# Robot-Power_V3_0.net
KiCad netlist of a schematic drawn in Altium Designer
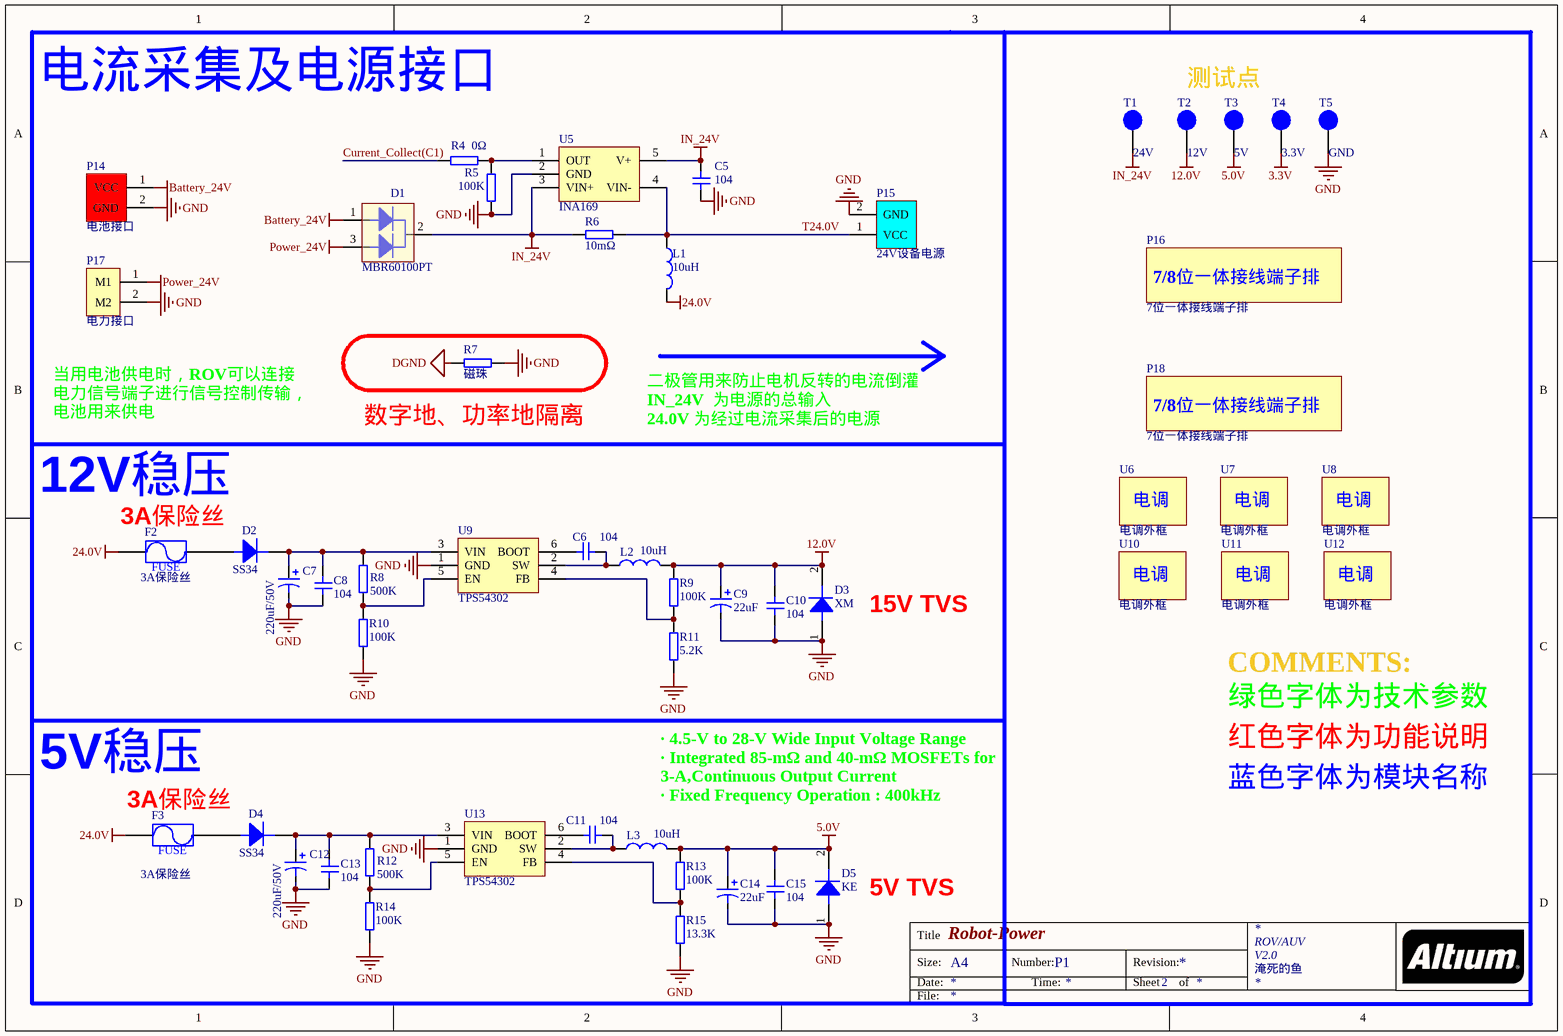
[diagram p0: Robot-Power V3.0.SchDoc]

(export (version "E")
  (design (tool "Eeschema 10.0.6"))
  (components
    (comp (ref "C5")
      (value "104")
      (footprint "0805C")
      (description "无极贴片电容")
      (libsource (lib "集大电协1.5") (part "Cap1"))
    )
    (comp (ref "C6")
      (value "104")
      (footprint "0805C")
      (description "无极贴片电容")
      (libsource (lib "集大电协1.5") (part "Cap1"))
    )
    (comp (ref "C7")
      (value "220uF/50V")
      (footprint "RB.1.2")
      (description "直插极性电容")
      (libsource (lib "集大电协1.5") (part "Cap3"))
    )
    (comp (ref "C8")
      (value "104")
      (footprint "0805C")
      (description "无极贴片电容")
      (libsource (lib "集大电协1.5") (part "Cap1"))
    )
    (comp (ref "C9")
      (value "22uF")
      (footprint "TAJ-C")
      (description "极性贴片电容")
      (libsource (lib "集大电协1.5") (part "Pol Cap"))
    )
    (comp (ref "C10")
      (value "104")
      (footprint "0805C")
      (description "无极贴片电容")
      (libsource (lib "集大电协1.5") (part "Cap1"))
    )
    (comp (ref "C11")
      (value "104")
      (footprint "0805C")
      (description "无极贴片电容")
      (libsource (lib "集大电协1.5") (part "Cap1"))
    )
    (comp (ref "C12")
      (value "220uF/50V")
      (footprint "RB.1.2")
      (description "直插极性电容")
      (libsource (lib "集大电协1.5") (part "Cap3"))
    )
    (comp (ref "C13")
      (value "104")
      (footprint "0805C")
      (description "无极贴片电容")
      (libsource (lib "集大电协1.5") (part "Cap1"))
    )
    (comp (ref "C14")
      (value "22uF")
      (footprint "TAJ-C")
      (description "极性贴片电容")
      (libsource (lib "集大电协1.5") (part "Pol Cap"))
    )
    (comp (ref "C15")
      (value "104")
      (footprint "0805C")
      (description "无极贴片电容")
      (libsource (lib "集大电协1.5") (part "Cap1"))
    )
    (comp (ref "D1")
      (value "MBR60100PT")
      (footprint "TO-247LS")
      (libsource (lib "集大电协1.5") (part "MBR60100PT"))
    )
    (comp (ref "D2")
      (value "SS34")
      (footprint "SMA/DO-214AC")
      (description "二极管")
      (libsource (lib "") (part "Diode_1"))
    )
    (comp (ref "D3")
      (value "XM")
      (footprint "SMBJ")
      (description "二极管")
      (libsource (lib "集大电协1.5") (part "Diode"))
    )
    (comp (ref "D4")
      (value "SS34")
      (footprint "SMA/DO-214AC")
      (description "二极管")
      (libsource (lib "") (part "Diode_1"))
    )
    (comp (ref "D5")
      (value "KE")
      (footprint "SMBJ")
      (description "二极管")
      (libsource (lib "集大电协1.5") (part "Diode"))
    )
    (comp (ref "F2")
      (value "3A保险丝")
      (footprint "FUSE-1206")
      (description "保险丝")
      (libsource (lib "集大电协1.2") (part "Fuse"))
    )
    (comp (ref "F3")
      (value "3A保险丝")
      (footprint "FUSE-1206")
      (description "保险丝")
      (libsource (lib "集大电协1.2") (part "Fuse"))
    )
    (comp (ref "L1")
      (value "10uH")
      (footprint "CDRH124")
      (description "电感")
      (libsource (lib "") (part "L_1"))
    )
    (comp (ref "L2")
      (value "10uH")
      (footprint "CDRH124")
      (description "电感")
      (libsource (lib "集大电协1.5") (part "L"))
    )
    (comp (ref "L3")
      (value "10uH")
      (footprint "CDRH124")
      (description "电感")
      (libsource (lib "集大电协1.5") (part "L"))
    )
    (comp (ref "P14") (value "电池接口") (footprint "XT60-F") (libsource (lib "集大电协1.5") (part "电源端子")))
    (comp (ref "P15") (value "24V设备电源") (footprint "XT60-F") (libsource (lib "集大电协1.5") (part "推进器电源")))
    (comp (ref "P16")
      (value "7位一体接线端子排")
      (footprint "7/8一体接线端子")
      (libsource (lib "集大电协1.5") (part "7位一体接线端子排"))
    )
    (comp (ref "P17")
      (value "电力接口")
      (footprint "XT60-F")
      (description "2PIN")
      (libsource (lib "集大电协1.5") (part "接线端子-2PIN"))
    )
    (comp (ref "P18")
      (value "7位一体接线端子排")
      (footprint "7/8一体接线端子")
      (libsource (lib "集大电协1.5") (part "7位一体接线端子排"))
    )
    (comp (ref "R4")
      (value "0Ω")
      (footprint "0805R")
      (description "电阻")
      (libsource (lib "集大电协1.5") (part "Res"))
    )
    (comp (ref "R5")
      (value "100K")
      (footprint "0805R")
      (description "电阻")
      (libsource (lib "集大电协1.5") (part "Res"))
    )
    (comp (ref "R6")
      (value "10mΩ")
      (footprint "2512R")
      (description "电阻")
      (libsource (lib "集大电协1.5") (part "Res"))
    )
    (comp (ref "R7")
      (value "磁珠")
      (footprint "1210R")
      (description "电阻")
      (libsource (lib "集大电协1.2") (part "Res"))
    )
    (comp (ref "R8")
      (value "500K")
      (footprint "0805R")
      (description "电阻")
      (libsource (lib "集大电协1.5") (part "Res"))
    )
    (comp (ref "R9")
      (value "100K")
      (footprint "0805R")
      (description "电阻")
      (libsource (lib "集大电协1.5") (part "Res"))
    )
    (comp (ref "R10")
      (value "100K")
      (footprint "0805R")
      (description "电阻")
      (libsource (lib "集大电协1.5") (part "Res"))
    )
    (comp (ref "R11")
      (value "5.2K")
      (footprint "0805R")
      (description "电阻")
      (libsource (lib "集大电协1.5") (part "Res"))
    )
    (comp (ref "R12")
      (value "500K")
      (footprint "0805R")
      (description "电阻")
      (libsource (lib "集大电协1.5") (part "Res"))
    )
    (comp (ref "R13")
      (value "100K")
      (footprint "0805R")
      (description "电阻")
      (libsource (lib "集大电协1.5") (part "Res"))
    )
    (comp (ref "R14")
      (value "100K")
      (footprint "0805R")
      (description "电阻")
      (libsource (lib "集大电协1.5") (part "Res"))
    )
    (comp (ref "R15")
      (value "13.3K")
      (footprint "0805R")
      (description "电阻")
      (libsource (lib "集大电协1.5") (part "Res"))
    )
    (comp (ref "T1")
      (value "24V")
      (footprint "HEADER 1")
      (description "测试点")
      (libsource (lib "集大电协1.2") (part "测试点"))
    )
    (comp (ref "T2")
      (value "12V")
      (footprint "HEADER 1")
      (description "测试点")
      (libsource (lib "集大电协1.2") (part "测试点"))
    )
    (comp (ref "T3")
      (value "5V")
      (footprint "HEADER 1")
      (description "测试点")
      (libsource (lib "集大电协1.2") (part "测试点"))
    )
    (comp (ref "T4")
      (value "3.3V")
      (footprint "HEADER 1")
      (description "测试点")
      (libsource (lib "集大电协1.2") (part "测试点"))
    )
    (comp (ref "T5")
      (value "GND")
      (footprint "HEADER 1")
      (description "测试点")
      (libsource (lib "集大电协1.2") (part "测试点"))
    )
    (comp (ref "U5") (value "INA169") (footprint "SOT23-5") (libsource (lib "集大电协1.5") (part "INA169")))
    (comp (ref "U6") (value "电调外框") (footprint "电调外框") (libsource (lib "集大电协1.5") (part "电调")))
    (comp (ref "U7") (value "电调外框") (footprint "电调外框") (libsource (lib "集大电协1.5") (part "电调")))
    (comp (ref "U8") (value "电调外框") (footprint "电调外框") (libsource (lib "集大电协1.5") (part "电调")))
    (comp (ref "U9") (value "TPS54302") (footprint "SOT23-6") (libsource (lib "集大电协1.5") (part "TPS54302")))
    (comp (ref "U10") (value "电调外框") (footprint "电调外框") (libsource (lib "集大电协1.5") (part "电调")))
    (comp (ref "U11") (value "电调外框") (footprint "电调外框") (libsource (lib "集大电协1.5") (part "电调")))
    (comp (ref "U12") (value "电调外框") (footprint "电调外框") (libsource (lib "集大电协1.5") (part "电调")))
    (comp (ref "U13") (value "TPS54302") (footprint "SOT23-6") (libsource (lib "集大电协1.5") (part "TPS54302")))
  )
  (nets
    (net (code "1") (name "/Current_Collect(C1)") (class "Default")
      (node (ref "R4") (pin "1") (pinfunction "1_1") (pintype "passive"))
    )
    (net (code "2") (name "/T24.0V") (class "Default")
      (node (ref "L1") (pin "1") (pinfunction "1_1") (pintype "passive"))
      (node (ref "P15") (pin "1") (pinfunction "VCC_1") (pintype "passive"))
      (node (ref "R6") (pin "1") (pinfunction "1_1") (pintype "passive"))
      (node (ref "U5") (pin "4") (pinfunction "VIN-_4") (pintype "passive"))
    )
    (net (code "3") (name "3.3V") (class "Default")
      (node (ref "T4") (pin "1") (pinfunction "1_1") (pintype "passive"))
    )
    (net (code "4") (name "5.0V") (class "Default")
      (node (ref "C14") (pin "1") (pinfunction "1_1") (pintype "passive"))
      (node (ref "C15") (pin "2") (pinfunction "2_2") (pintype "passive"))
      (node (ref "D5") (pin "2") (pinfunction "2_2") (pintype "passive"))
      (node (ref "L3") (pin "2") (pinfunction "2_2") (pintype "passive"))
      (node (ref "R13") (pin "2") (pinfunction "2_2") (pintype "passive"))
      (node (ref "T3") (pin "1") (pinfunction "1_1") (pintype "passive"))
    )
    (net (code "5") (name "12.0V") (class "Default")
      (node (ref "C10") (pin "2") (pinfunction "2_2") (pintype "passive"))
      (node (ref "C9") (pin "1") (pinfunction "1_1") (pintype "passive"))
      (node (ref "D3") (pin "2") (pinfunction "2_2") (pintype "passive"))
      (node (ref "L2") (pin "2") (pinfunction "2_2") (pintype "passive"))
      (node (ref "R9") (pin "2") (pinfunction "2_2") (pintype "passive"))
      (node (ref "T2") (pin "1") (pinfunction "1_1") (pintype "passive"))
    )
    (net (code "6") (name "24.0V") (class "Default")
      (node (ref "F2") (pin "1") (pinfunction "1_1") (pintype "passive"))
      (node (ref "F3") (pin "1") (pinfunction "1_1") (pintype "passive"))
      (node (ref "L1") (pin "2") (pinfunction "2_2") (pintype "passive"))
    )
    (net (code "7") (name "Battery_24V") (class "Default")
      (node (ref "D1") (pin "1") (pintype "passive"))
      (node (ref "P14") (pin "1") (pinfunction "VCC_1") (pintype "passive"))
    )
    (net (code "8") (name "DGND") (class "Default")
      (node (ref "R7") (pin "2") (pinfunction "2_2") (pintype "passive"))
    )
    (net (code "9") (name "GND") (class "Default")
      (node (ref "C10") (pin "1") (pinfunction "1_1") (pintype "passive"))
      (node (ref "C12") (pin "2") (pinfunction "2_2") (pintype "passive"))
      (node (ref "C13") (pin "1") (pinfunction "1_1") (pintype "passive"))
      (node (ref "C14") (pin "2") (pinfunction "2_2") (pintype "passive"))
      (node (ref "C15") (pin "1") (pinfunction "1_1") (pintype "passive"))
      (node (ref "C5") (pin "1") (pinfunction "1_1") (pintype "passive"))
      (node (ref "C7") (pin "2") (pinfunction "2_2") (pintype "passive"))
      (node (ref "C8") (pin "1") (pinfunction "1_1") (pintype "passive"))
      (node (ref "C9") (pin "2") (pinfunction "2_2") (pintype "passive"))
      (node (ref "D3") (pin "1") (pintype "passive"))
      (node (ref "D5") (pin "1") (pintype "passive"))
      (node (ref "P14") (pin "2") (pinfunction "GND_2") (pintype "passive"))
      (node (ref "P15") (pin "2") (pinfunction "GND_2") (pintype "passive"))
      (node (ref "P17") (pin "2") (pinfunction "M2_2") (pintype "passive"))
      (node (ref "R10") (pin "1") (pinfunction "1_1") (pintype "passive"))
      (node (ref "R11") (pin "1") (pinfunction "1_1") (pintype "passive"))
      (node (ref "R14") (pin "1") (pinfunction "1_1") (pintype "passive"))
      (node (ref "R15") (pin "1") (pinfunction "1_1") (pintype "passive"))
      (node (ref "R5") (pin "2") (pinfunction "2_2") (pintype "passive"))
      (node (ref "R7") (pin "1") (pinfunction "1_1") (pintype "passive"))
      (node (ref "T5") (pin "1") (pinfunction "1_1") (pintype "passive"))
      (node (ref "U13") (pin "1") (pinfunction "GND_1") (pintype "passive"))
      (node (ref "U5") (pin "2") (pinfunction "GND_2") (pintype "passive"))
      (node (ref "U9") (pin "1") (pinfunction "GND_1") (pintype "passive"))
    )
    (net (code "10") (name "IN_24V") (class "Default")
      (node (ref "C5") (pin "2") (pinfunction "2_2") (pintype "passive"))
      (node (ref "D1") (pin "2") (pinfunction "2_2") (pintype "passive"))
      (node (ref "R6") (pin "2") (pinfunction "2_2") (pintype "passive"))
      (node (ref "T1") (pin "1") (pinfunction "1_1") (pintype "passive"))
      (node (ref "U5") (pin "3") (pinfunction "VIN+_3") (pintype "passive"))
      (node (ref "U5") (pin "5") (pinfunction "V+_5") (pintype "passive"))
    )
    (net (code "11") (name "Net-(D2-Pad1)") (class "Default")
      (node (ref "D2") (pin "1") (pintype "passive"))
      (node (ref "F2") (pin "2") (pinfunction "2_2") (pintype "passive"))
    )
    (net (code "12") (name "Net-(D4-Pad1)") (class "Default")
      (node (ref "D4") (pin "1") (pintype "passive"))
      (node (ref "F3") (pin "2") (pinfunction "2_2") (pintype "passive"))
    )
    (net (code "13") (name "Net-(U5-OUT)") (class "Default")
      (node (ref "R4") (pin "2") (pinfunction "2_2") (pintype "passive"))
      (node (ref "R5") (pin "1") (pinfunction "1_1") (pintype "passive"))
      (node (ref "U5") (pin "1") (pinfunction "OUT_1") (pintype "passive"))
    )
    (net (code "14") (name "Net-(U9-BOOT)") (class "Default")
      (node (ref "C6") (pin "2") (pinfunction "2_2") (pintype "passive"))
      (node (ref "U9") (pin "6") (pinfunction "BOOT_6") (pintype "passive"))
    )
    (net (code "15") (name "Net-(U9-EN)") (class "Default")
      (node (ref "R10") (pin "2") (pinfunction "2_2") (pintype "passive"))
      (node (ref "R8") (pin "1") (pinfunction "1_1") (pintype "passive"))
      (node (ref "U9") (pin "5") (pinfunction "EN_5") (pintype "passive"))
    )
    (net (code "16") (name "Net-(U9-FB)") (class "Default")
      (node (ref "R11") (pin "2") (pinfunction "2_2") (pintype "passive"))
      (node (ref "R9") (pin "1") (pinfunction "1_1") (pintype "passive"))
      (node (ref "U9") (pin "4") (pinfunction "FB_4") (pintype "passive"))
    )
    (net (code "17") (name "Net-(U9-SW)") (class "Default")
      (node (ref "C6") (pin "1") (pinfunction "1_1") (pintype "passive"))
      (node (ref "L2") (pin "1") (pinfunction "1_1") (pintype "passive"))
      (node (ref "U9") (pin "2") (pinfunction "SW_2") (pintype "passive"))
    )
    (net (code "18") (name "Net-(U9-VIN)") (class "Default")
      (node (ref "C7") (pin "1") (pinfunction "1_1") (pintype "passive"))
      (node (ref "C8") (pin "2") (pinfunction "2_2") (pintype "passive"))
      (node (ref "D2") (pin "2") (pinfunction "2_2") (pintype "passive"))
      (node (ref "R8") (pin "2") (pinfunction "2_2") (pintype "passive"))
      (node (ref "U9") (pin "3") (pinfunction "VIN_3") (pintype "passive"))
    )
    (net (code "19") (name "Net-(U13-BOOT)") (class "Default")
      (node (ref "C11") (pin "2") (pinfunction "2_2") (pintype "passive"))
      (node (ref "U13") (pin "6") (pinfunction "BOOT_6") (pintype "passive"))
    )
    (net (code "20") (name "Net-(U13-EN)") (class "Default")
      (node (ref "R12") (pin "1") (pinfunction "1_1") (pintype "passive"))
      (node (ref "R14") (pin "2") (pinfunction "2_2") (pintype "passive"))
      (node (ref "U13") (pin "5") (pinfunction "EN_5") (pintype "passive"))
    )
    (net (code "21") (name "Net-(U13-FB)") (class "Default")
      (node (ref "R13") (pin "1") (pinfunction "1_1") (pintype "passive"))
      (node (ref "R15") (pin "2") (pinfunction "2_2") (pintype "passive"))
      (node (ref "U13") (pin "4") (pinfunction "FB_4") (pintype "passive"))
    )
    (net (code "22") (name "Net-(U13-SW)") (class "Default")
      (node (ref "C11") (pin "1") (pinfunction "1_1") (pintype "passive"))
      (node (ref "L3") (pin "1") (pinfunction "1_1") (pintype "passive"))
      (node (ref "U13") (pin "2") (pinfunction "SW_2") (pintype "passive"))
    )
    (net (code "23") (name "Net-(U13-VIN)") (class "Default")
      (node (ref "C12") (pin "1") (pinfunction "1_1") (pintype "passive"))
      (node (ref "C13") (pin "2") (pinfunction "2_2") (pintype "passive"))
      (node (ref "D4") (pin "2") (pinfunction "2_2") (pintype "passive"))
      (node (ref "R12") (pin "2") (pinfunction "2_2") (pintype "passive"))
      (node (ref "U13") (pin "3") (pinfunction "VIN_3") (pintype "passive"))
    )
    (net (code "24") (name "Power_24V") (class "Default")
      (node (ref "D1") (pin "3") (pintype "passive"))
      (node (ref "P17") (pin "1") (pinfunction "M1_1") (pintype "passive"))
    )
  )
)
